# eeZee_microSD.net
KiCad netlist of a schematic drawn in EAGLE
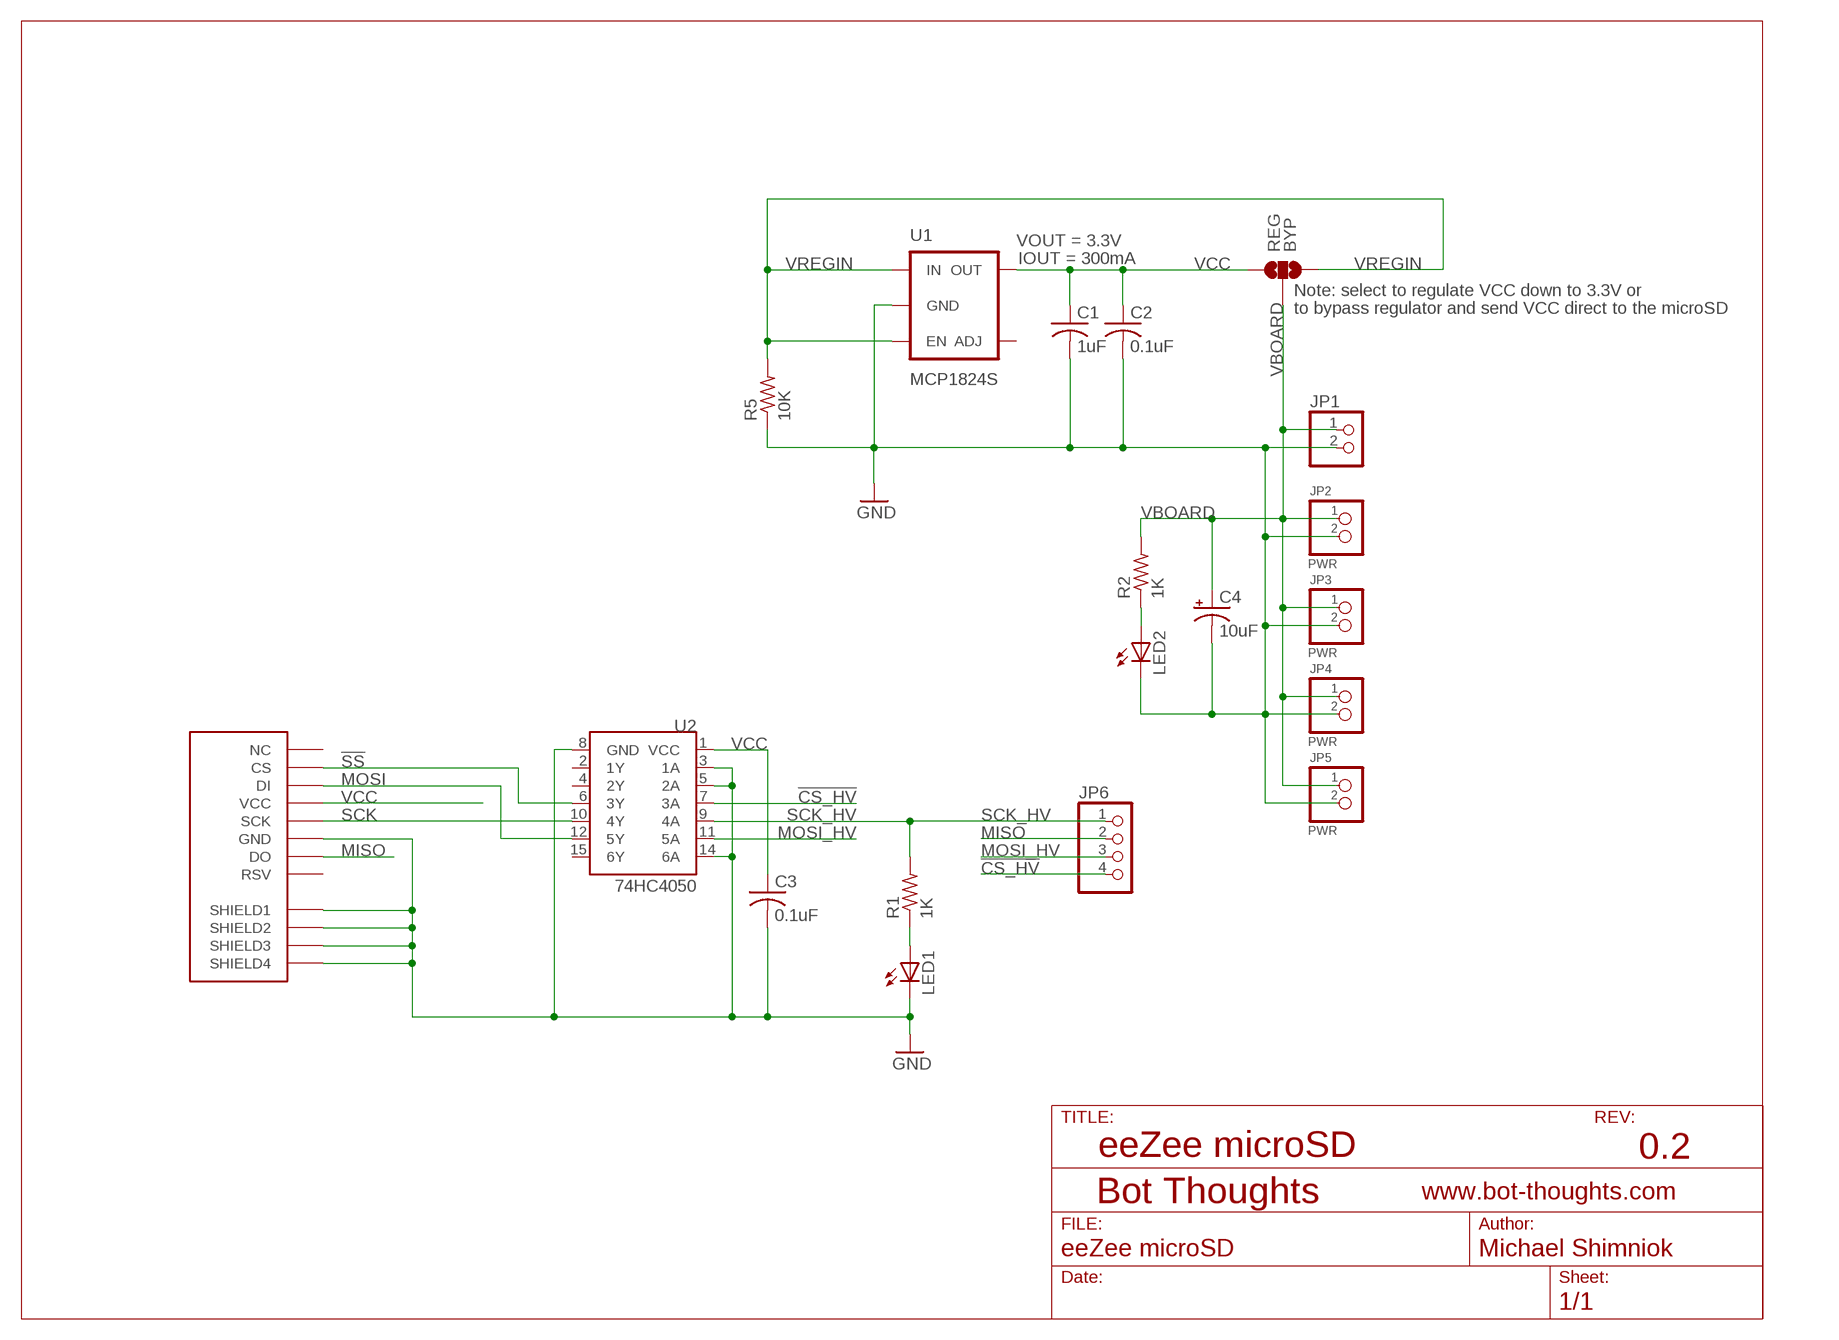
[diagram p0: schematic, sheet 1]

(export (version "E")
  (design (tool "Eeschema 10.0.6"))
  (components
    (comp (ref "C1")
      (value "1uF")
      (footprint "eagle-import:C0603")
      (fields (field (name "PARTNO") "LMK107B7105KA-T"))
      (libsource (lib "eagle-import") (part "C-USC0603"))
    )
    (comp (ref "C2")
      (value "0.1uF")
      (footprint "eagle-import:C0603")
      (fields (field (name "PARTNO") "LMK107B7105KA-T"))
      (libsource (lib "eagle-import") (part "C-USC0603"))
    )
    (comp (ref "C3")
      (value "0.1uF")
      (footprint "eagle-import:C0603")
      (fields (field (name "PARTNO") "LMK107B7105KA-T"))
      (libsource (lib "eagle-import") (part "C-USC0603"))
    )
    (comp (ref "C4")
      (value "10uF")
      (footprint "eagle-import:SMC_B")
      (fields (field (name "PARTNO") "LMK107B7105KA-T"))
      (libsource (lib "eagle-import") (part "CPOL-USSMCB"))
    )
    (comp (ref "JP1")
      (value "PINHD-1X02_2.54-S")
      (footprint "eagle-import:1X02-S")
      (libsource (lib "eagle-import") (part "PINHD-1X02_2.54-S"))
    )
    (comp (ref "JP2")
      (value "PWR")
      (footprint "eagle-import:BIGPIN-2")
      (libsource (lib "eagle-import") (part "PINHEAD-2BIG"))
    )
    (comp (ref "JP3")
      (value "PWR")
      (footprint "eagle-import:BIGPIN-2")
      (libsource (lib "eagle-import") (part "PINHEAD-2BIG"))
    )
    (comp (ref "JP4")
      (value "PWR")
      (footprint "eagle-import:BIGPIN-2")
      (libsource (lib "eagle-import") (part "PINHEAD-2BIG"))
    )
    (comp (ref "JP5")
      (value "PWR")
      (footprint "eagle-import:BIGPIN-2")
      (libsource (lib "eagle-import") (part "PINHEAD-2BIG"))
    )
    (comp (ref "JP6")
      (value "PINHD-1X04_2.54-S")
      (footprint "eagle-import:1X04-S")
      (libsource (lib "eagle-import") (part "PINHD-1X04_2.54-S"))
    )
    (comp (ref "LED1")
      (value "LEDCHIPLED_0805")
      (footprint "eagle-import:CHIPLED_0805")
      (libsource (lib "eagle-import") (part "LEDCHIPLED_0805"))
    )
    (comp (ref "LED2")
      (value "LEDCHIPLED_0805")
      (footprint "eagle-import:CHIPLED_0805")
      (libsource (lib "eagle-import") (part "LEDCHIPLED_0805"))
    )
    (comp (ref "R1")
      (value "1K")
      (footprint "eagle-import:R0603")
      (fields (field (name "PARTNO") "ERJ-3GEYJ103V"))
      (libsource (lib "eagle-import") (part "R-US_R0603"))
    )
    (comp (ref "R2")
      (value "1K")
      (footprint "eagle-import:R0603")
      (fields (field (name "PARTNO") "ERJ-3GEYJ103V"))
      (libsource (lib "eagle-import") (part "R-US_R0603"))
    )
    (comp (ref "R5")
      (value "10K")
      (footprint "eagle-import:R0603")
      (fields (field (name "PARTNO") "ERJ-3GEYJ103V"))
      (libsource (lib "eagle-import") (part "R-US_R0603"))
    )
    (comp (ref "REG")
      (value "BYP")
      (footprint "eagle-import:SJ_3")
      (libsource (lib "eagle-import") (part "SOLDERJUMPER_2WAYS"))
    )
    (comp (ref "U$1")
      (value "MICROSD_TFLASH")
      (footprint "eagle-import:TFLASH_CP-0000-086")
      (libsource (lib "eagle-import") (part "MICROSD_TFLASH"))
    )
    (comp (ref "U1")
      (value "MCP1824S")
      (footprint "eagle-import:SOT23-5")
      (fields
        (field (name "IOUT") "300mA")
        (field (name "PARTNO") "MCP1824ST-3302E/DB")
        (field (name "VOUT") "3.3V")
      )
      (libsource (lib "eagle-import") (part "MCP1824"))
    )
    (comp (ref "U2")
      (value "74HC4050")
      (footprint "eagle-import:SO016")
      (libsource (lib "eagle-import") (part "HEX_CONVERTER"))
    )
  )
  (nets
    (net (code "1") (name "/MISO") (class "Default")
      (node (ref "JP6") (pin "2") (pinfunction "2_2") (pintype "passive"))
      (node (ref "U$1") (pin "DO") (pinfunction "DO_DO") (pintype "bidirectional"))
    )
    (net (code "2") (name "/MOSI") (class "Default")
      (node (ref "U$1") (pin "DI") (pinfunction "DI_DI") (pintype "bidirectional"))
      (node (ref "U2") (pin "12") (pinfunction "5Y_12") (pintype "bidirectional"))
    )
    (net (code "3") (name "/MOSI_HV") (class "Default")
      (node (ref "JP6") (pin "3") (pinfunction "3_3") (pintype "passive"))
      (node (ref "U2") (pin "11") (pinfunction "5A_11") (pintype "bidirectional"))
    )
    (net (code "4") (name "/SCK") (class "Default")
      (node (ref "U$1") (pin "SCLK") (pinfunction "SCK_SCLK") (pintype "bidirectional"))
      (node (ref "U2") (pin "10") (pinfunction "4Y_10") (pintype "bidirectional"))
    )
    (net (code "5") (name "/SCK_HV") (class "Default")
      (node (ref "JP6") (pin "1") (pinfunction "1_1") (pintype "passive"))
      (node (ref "R1") (pin "2") (pinfunction "2_2") (pintype "passive"))
      (node (ref "U2") (pin "9") (pinfunction "4A_9") (pintype "bidirectional"))
    )
    (net (code "6") (name "/VBOARD") (class "Default")
      (node (ref "C4") (pin "+") (pinfunction "+_+") (pintype "passive"))
      (node (ref "JP1") (pin "1") (pinfunction "1_1") (pintype "passive"))
      (node (ref "JP2") (pin "P$1") (pinfunction "1_P$1") (pintype "bidirectional"))
      (node (ref "JP3") (pin "P$1") (pinfunction "1_P$1") (pintype "bidirectional"))
      (node (ref "JP4") (pin "P$1") (pinfunction "1_P$1") (pintype "bidirectional"))
      (node (ref "JP5") (pin "P$1") (pinfunction "1_P$1") (pintype "bidirectional"))
      (node (ref "R2") (pin "2") (pinfunction "2_2") (pintype "passive"))
      (node (ref "REG") (pin "2") (pinfunction "2_2") (pintype "passive"))
    )
    (net (code "7") (name "/VCC") (class "Default")
      (node (ref "C1") (pin "1") (pinfunction "1_1") (pintype "passive"))
      (node (ref "C2") (pin "1") (pinfunction "1_1") (pintype "passive"))
      (node (ref "C3") (pin "1") (pinfunction "1_1") (pintype "passive"))
      (node (ref "REG") (pin "1") (pinfunction "1_1") (pintype "passive"))
      (node (ref "U$1") (pin "VDD") (pinfunction "VCC_VDD") (pintype "bidirectional"))
      (node (ref "U1") (pin "5") (pinfunction "OUT_5") (pintype "passive"))
      (node (ref "U2") (pin "1") (pinfunction "VCC_1") (pintype "bidirectional"))
    )
    (net (code "8") (name "/VREGIN") (class "Default")
      (node (ref "R5") (pin "2") (pinfunction "2_2") (pintype "passive"))
      (node (ref "REG") (pin "3") (pinfunction "3_3") (pintype "passive"))
      (node (ref "U1") (pin "1") (pinfunction "IN_1") (pintype "input"))
      (node (ref "U1") (pin "3") (pinfunction "EN_3") (pintype "input"))
    )
    (net (code "9") (name "/~{CS_HV}") (class "Default")
      (node (ref "JP6") (pin "4") (pinfunction "4_4") (pintype "passive"))
      (node (ref "U2") (pin "7") (pinfunction "3A_7") (pintype "bidirectional"))
    )
    (net (code "10") (name "/~{SS}") (class "Default")
      (node (ref "U$1") (pin "CS") (pinfunction "CS_CS") (pintype "bidirectional"))
      (node (ref "U2") (pin "6") (pinfunction "3Y_6") (pintype "bidirectional"))
    )
    (net (code "11") (name "GND") (class "Default")
      (node (ref "C1") (pin "2") (pinfunction "2_2") (pintype "passive"))
      (node (ref "C2") (pin "2") (pinfunction "2_2") (pintype "passive"))
      (node (ref "C3") (pin "2") (pinfunction "2_2") (pintype "passive"))
      (node (ref "C4") (pin "-") (pinfunction "-_-") (pintype "passive"))
      (node (ref "JP1") (pin "2") (pinfunction "2_2") (pintype "passive"))
      (node (ref "JP2") (pin "P$2") (pinfunction "2_P$2") (pintype "bidirectional"))
      (node (ref "JP3") (pin "P$2") (pinfunction "2_P$2") (pintype "bidirectional"))
      (node (ref "JP4") (pin "P$2") (pinfunction "2_P$2") (pintype "bidirectional"))
      (node (ref "JP5") (pin "P$2") (pinfunction "2_P$2") (pintype "bidirectional"))
      (node (ref "LED1") (pin "C") (pinfunction "C_C") (pintype "passive"))
      (node (ref "LED2") (pin "C") (pinfunction "C_C") (pintype "passive"))
      (node (ref "R5") (pin "1") (pinfunction "1_1") (pintype "passive"))
      (node (ref "U$1") (pin "GND") (pinfunction "GND_GND") (pintype "bidirectional"))
      (node (ref "U$1") (pin "SHIELD1") (pinfunction "SHIELD1_SHIELD1") (pintype "bidirectional"))
      (node (ref "U$1") (pin "SHIELD2") (pinfunction "SHIELD2_SHIELD2") (pintype "bidirectional"))
      (node (ref "U$1") (pin "SHIELD3") (pinfunction "SHIELD3_SHIELD3") (pintype "bidirectional"))
      (node (ref "U$1") (pin "SHIELD4") (pinfunction "SHIELD4_SHIELD4") (pintype "bidirectional"))
      (node (ref "U1") (pin "2") (pinfunction "GND_2") (pintype "input"))
      (node (ref "U2") (pin "14") (pinfunction "6A_14") (pintype "bidirectional"))
      (node (ref "U2") (pin "3") (pinfunction "1A_3") (pintype "bidirectional"))
      (node (ref "U2") (pin "5") (pinfunction "2A_5") (pintype "bidirectional"))
      (node (ref "U2") (pin "8") (pinfunction "GND_8") (pintype "bidirectional"))
    )
    (net (code "12") (name "Net-(LED1-PadA)") (class "Default")
      (node (ref "LED1") (pin "A") (pinfunction "A_A") (pintype "passive"))
      (node (ref "R1") (pin "1") (pinfunction "1_1") (pintype "passive"))
    )
    (net (code "13") (name "Net-(LED2-PadA)") (class "Default")
      (node (ref "LED2") (pin "A") (pinfunction "A_A") (pintype "passive"))
      (node (ref "R2") (pin "1") (pinfunction "1_1") (pintype "passive"))
    )
    (net (code "14") (name "unconnected-(U$1-PadNC)") (class "Default")
      (node (ref "U$1") (pin "NC") (pinfunction "NC_NC") (pintype "bidirectional"))
    )
    (net (code "15") (name "unconnected-(U$1-PadRSV)") (class "Default")
      (node (ref "U$1") (pin "RSV") (pinfunction "RSV_RSV") (pintype "bidirectional"))
    )
    (net (code "16") (name "unconnected-(U1-ADJ-Pad4)") (class "Default")
      (node (ref "U1") (pin "4") (pinfunction "ADJ_4") (pintype "input"))
    )
    (net (code "17") (name "unconnected-(U2-1Y-Pad2)") (class "Default")
      (node (ref "U2") (pin "2") (pinfunction "1Y_2") (pintype "bidirectional"))
    )
    (net (code "18") (name "unconnected-(U2-2Y-Pad4)") (class "Default")
      (node (ref "U2") (pin "4") (pinfunction "2Y_4") (pintype "bidirectional"))
    )
    (net (code "19") (name "unconnected-(U2-6Y-Pad15)") (class "Default")
      (node (ref "U2") (pin "15") (pinfunction "6Y_15") (pintype "bidirectional"))
    )
  )
)
